# peephole.net
KiCad netlist of a schematic drawn in EAGLE
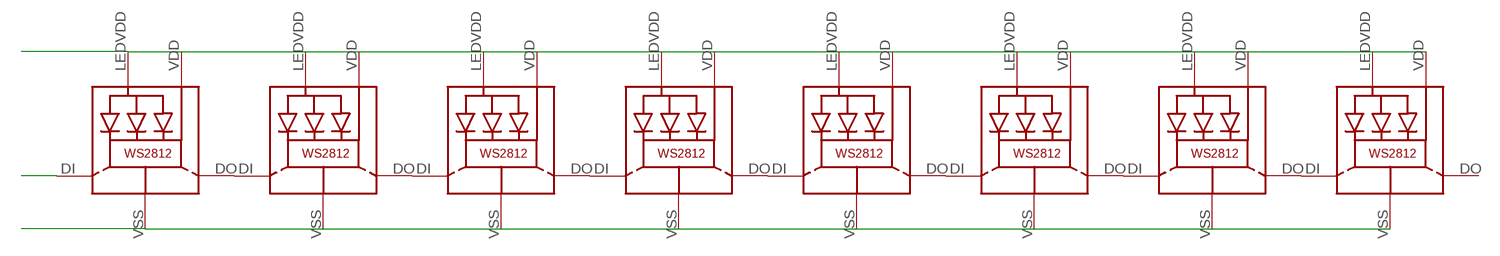
[diagram p0: schematic, sheet 1]

(export (version "E")
  (design (tool "Eeschema 10.0.6"))
  (components
    (comp (ref "LED1")
      (value "WS2812")
      (footprint "eagle-import:WS2812")
      (libsource (lib "eagle-import") (part "WS2812"))
    )
    (comp (ref "LED2")
      (value "WS2812")
      (footprint "eagle-import:WS2812")
      (libsource (lib "eagle-import") (part "WS2812"))
    )
    (comp (ref "LED3")
      (value "WS2812")
      (footprint "eagle-import:WS2812")
      (libsource (lib "eagle-import") (part "WS2812"))
    )
    (comp (ref "LED4")
      (value "WS2812")
      (footprint "eagle-import:WS2812")
      (libsource (lib "eagle-import") (part "WS2812"))
    )
    (comp (ref "LED5")
      (value "WS2812")
      (footprint "eagle-import:WS2812")
      (libsource (lib "eagle-import") (part "WS2812"))
    )
    (comp (ref "LED6")
      (value "WS2812")
      (footprint "eagle-import:WS2812")
      (libsource (lib "eagle-import") (part "WS2812"))
    )
    (comp (ref "LED7")
      (value "WS2812")
      (footprint "eagle-import:WS2812")
      (libsource (lib "eagle-import") (part "WS2812"))
    )
    (comp (ref "LED8")
      (value "WS2812")
      (footprint "eagle-import:WS2812")
      (libsource (lib "eagle-import") (part "WS2812"))
    )
  )
  (nets
    (net (code "1") (name "Net-(LED1-GND)") (class "Default")
      (node (ref "LED1") (pin "VSS") (pinfunction "GND_VSS") (pintype "power_in"))
      (node (ref "LED2") (pin "VSS") (pinfunction "GND_VSS") (pintype "power_in"))
      (node (ref "LED3") (pin "VSS") (pinfunction "GND_VSS") (pintype "power_in"))
      (node (ref "LED4") (pin "VSS") (pinfunction "GND_VSS") (pintype "power_in"))
      (node (ref "LED5") (pin "VSS") (pinfunction "GND_VSS") (pintype "power_in"))
      (node (ref "LED6") (pin "VSS") (pinfunction "GND_VSS") (pintype "power_in"))
      (node (ref "LED7") (pin "VSS") (pinfunction "GND_VSS") (pintype "power_in"))
      (node (ref "LED8") (pin "VSS") (pinfunction "GND_VSS") (pintype "power_in"))
    )
    (net (code "2") (name "Net-(LED1-PadDO)") (class "Default")
      (node (ref "LED1") (pin "DO") (pinfunction "DO_DO") (pintype "output"))
      (node (ref "LED2") (pin "DI") (pinfunction "DI_DI") (pintype "input"))
    )
    (net (code "3") (name "Net-(LED1-PadLEDVDD)") (class "Default")
      (node (ref "LED1") (pin "LEDVDD") (pinfunction "LEDVDD_LEDVDD") (pintype "power_in"))
      (node (ref "LED1") (pin "VDD") (pinfunction "VDD_VDD") (pintype "power_in"))
      (node (ref "LED2") (pin "LEDVDD") (pinfunction "LEDVDD_LEDVDD") (pintype "power_in"))
      (node (ref "LED2") (pin "VDD") (pinfunction "VDD_VDD") (pintype "power_in"))
      (node (ref "LED3") (pin "LEDVDD") (pinfunction "LEDVDD_LEDVDD") (pintype "power_in"))
      (node (ref "LED3") (pin "VDD") (pinfunction "VDD_VDD") (pintype "power_in"))
      (node (ref "LED4") (pin "LEDVDD") (pinfunction "LEDVDD_LEDVDD") (pintype "power_in"))
      (node (ref "LED4") (pin "VDD") (pinfunction "VDD_VDD") (pintype "power_in"))
      (node (ref "LED5") (pin "LEDVDD") (pinfunction "LEDVDD_LEDVDD") (pintype "power_in"))
      (node (ref "LED5") (pin "VDD") (pinfunction "VDD_VDD") (pintype "power_in"))
      (node (ref "LED6") (pin "LEDVDD") (pinfunction "LEDVDD_LEDVDD") (pintype "power_in"))
      (node (ref "LED6") (pin "VDD") (pinfunction "VDD_VDD") (pintype "power_in"))
      (node (ref "LED7") (pin "LEDVDD") (pinfunction "LEDVDD_LEDVDD") (pintype "power_in"))
      (node (ref "LED7") (pin "VDD") (pinfunction "VDD_VDD") (pintype "power_in"))
      (node (ref "LED8") (pin "LEDVDD") (pinfunction "LEDVDD_LEDVDD") (pintype "power_in"))
      (node (ref "LED8") (pin "VDD") (pinfunction "VDD_VDD") (pintype "power_in"))
    )
    (net (code "4") (name "Net-(LED2-PadDO)") (class "Default")
      (node (ref "LED2") (pin "DO") (pinfunction "DO_DO") (pintype "output"))
      (node (ref "LED3") (pin "DI") (pinfunction "DI_DI") (pintype "input"))
    )
    (net (code "5") (name "Net-(LED3-PadDO)") (class "Default")
      (node (ref "LED3") (pin "DO") (pinfunction "DO_DO") (pintype "output"))
      (node (ref "LED4") (pin "DI") (pinfunction "DI_DI") (pintype "input"))
    )
    (net (code "6") (name "Net-(LED4-PadDO)") (class "Default")
      (node (ref "LED4") (pin "DO") (pinfunction "DO_DO") (pintype "output"))
      (node (ref "LED5") (pin "DI") (pinfunction "DI_DI") (pintype "input"))
    )
    (net (code "7") (name "Net-(LED5-PadDO)") (class "Default")
      (node (ref "LED5") (pin "DO") (pinfunction "DO_DO") (pintype "output"))
      (node (ref "LED6") (pin "DI") (pinfunction "DI_DI") (pintype "input"))
    )
    (net (code "8") (name "Net-(LED6-PadDO)") (class "Default")
      (node (ref "LED6") (pin "DO") (pinfunction "DO_DO") (pintype "output"))
      (node (ref "LED7") (pin "DI") (pinfunction "DI_DI") (pintype "input"))
    )
    (net (code "9") (name "Net-(LED7-PadDO)") (class "Default")
      (node (ref "LED7") (pin "DO") (pinfunction "DO_DO") (pintype "output"))
      (node (ref "LED8") (pin "DI") (pinfunction "DI_DI") (pintype "input"))
    )
    (net (code "10") (name "unconnected-(LED1-PadDI)") (class "Default")
      (node (ref "LED1") (pin "DI") (pinfunction "DI_DI") (pintype "input"))
    )
    (net (code "11") (name "unconnected-(LED8-PadDO)") (class "Default")
      (node (ref "LED8") (pin "DO") (pinfunction "DO_DO") (pintype "output"))
    )
  )
)
